# DigitalOutputs.net
KiCad netlist of a schematic drawn in Altium Designer
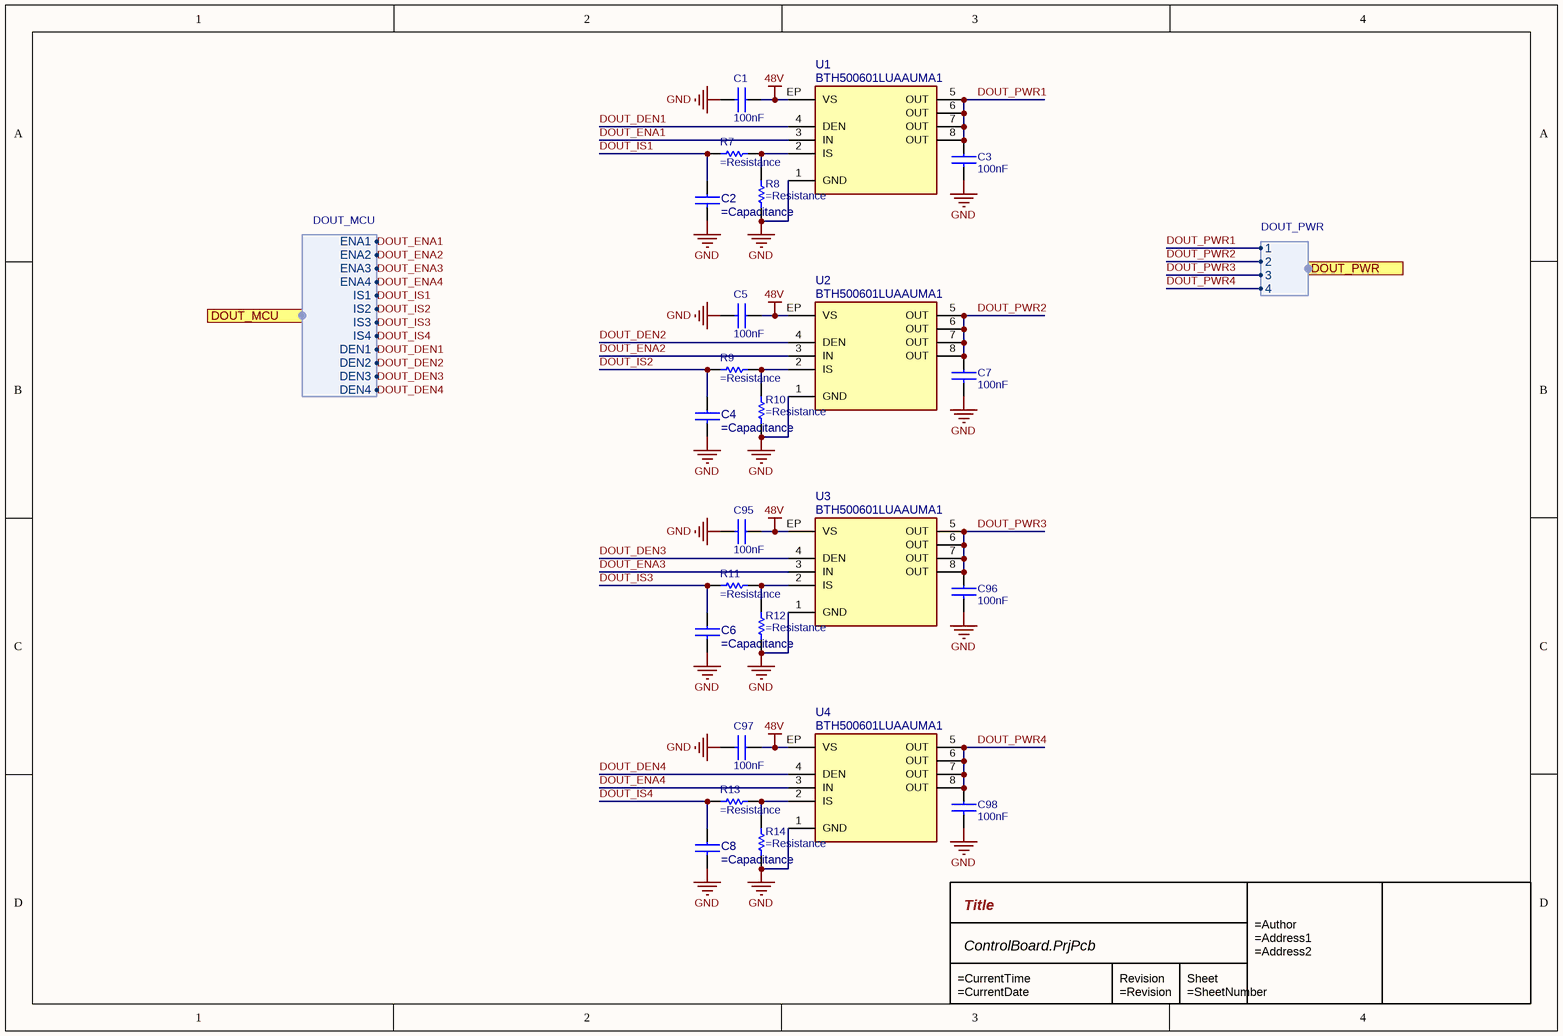
[diagram p0: DigitalOutputs.SchDoc]

(export (version "E")
  (design (tool "Eeschema 10.0.6"))
  (components
    (comp (ref "C1")
      (value "100nF")
      (footprint "C0603")
      (description "CAP CER 0.1UF 100V X7R 0603")
      (fields
        (field (name "MANUFACTURER") "Yageo")
        (field (name "MANUFACTURER PART NUMBER") "CC0603KRX7R0BB104")
      )
      (libsource (lib "Capacitors") (part "CAP0603-0.1uF-100V"))
    )
    (comp (ref "C2")
      (value "~")
      (footprint "C0402")
      (description "CAP CER 0.1UF 50V X7R 0402")
      (fields
        (field (name "MANUFACTURER") "Walsin Technologies")
        (field (name "MANUFACTURER PART NUMBER") "0402B104K500CT")
      )
      (libsource (lib "HerosLib") (part "CAP0402-0.1uF-50V"))
    )
    (comp (ref "C3")
      (value "100nF")
      (footprint "C0603")
      (description "CAP CER 0.1UF 100V X7R 0603")
      (fields
        (field (name "MANUFACTURER") "Yageo")
        (field (name "MANUFACTURER PART NUMBER") "CC0603KRX7R0BB104")
      )
      (libsource (lib "Capacitors") (part "CAP0603-0.1uF-100V"))
    )
    (comp (ref "C4")
      (value "~")
      (footprint "C0402")
      (description "CAP CER 0.1UF 50V X7R 0402")
      (fields
        (field (name "MANUFACTURER") "Walsin Technologies")
        (field (name "MANUFACTURER PART NUMBER") "0402B104K500CT")
      )
      (libsource (lib "HerosLib") (part "CAP0402-0.1uF-50V"))
    )
    (comp (ref "C5")
      (value "100nF")
      (footprint "C0603")
      (description "CAP CER 0.1UF 100V X7R 0603")
      (fields
        (field (name "MANUFACTURER") "Yageo")
        (field (name "MANUFACTURER PART NUMBER") "CC0603KRX7R0BB104")
      )
      (libsource (lib "Capacitors") (part "CAP0603-0.1uF-100V"))
    )
    (comp (ref "C6")
      (value "~")
      (footprint "C0402")
      (description "CAP CER 0.1UF 50V X7R 0402")
      (fields
        (field (name "MANUFACTURER") "Walsin Technologies")
        (field (name "MANUFACTURER PART NUMBER") "0402B104K500CT")
      )
      (libsource (lib "HerosLib") (part "CAP0402-0.1uF-50V"))
    )
    (comp (ref "C7")
      (value "100nF")
      (footprint "C0603")
      (description "CAP CER 0.1UF 100V X7R 0603")
      (fields
        (field (name "MANUFACTURER") "Yageo")
        (field (name "MANUFACTURER PART NUMBER") "CC0603KRX7R0BB104")
      )
      (libsource (lib "Capacitors") (part "CAP0603-0.1uF-100V"))
    )
    (comp (ref "C8")
      (value "~")
      (footprint "C0402")
      (description "CAP CER 0.1UF 50V X7R 0402")
      (fields
        (field (name "MANUFACTURER") "Walsin Technologies")
        (field (name "MANUFACTURER PART NUMBER") "0402B104K500CT")
      )
      (libsource (lib "HerosLib") (part "CAP0402-0.1uF-50V"))
    )
    (comp (ref "C95")
      (value "100nF")
      (footprint "C0603")
      (description "CAP CER 0.1UF 100V X7R 0603")
      (fields
        (field (name "MANUFACTURER") "Yageo")
        (field (name "MANUFACTURER PART NUMBER") "CC0603KRX7R0BB104")
      )
      (libsource (lib "Capacitors") (part "CAP0603-0.1uF-100V"))
    )
    (comp (ref "C96")
      (value "100nF")
      (footprint "C0603")
      (description "CAP CER 0.1UF 100V X7R 0603")
      (fields
        (field (name "MANUFACTURER") "Yageo")
        (field (name "MANUFACTURER PART NUMBER") "CC0603KRX7R0BB104")
      )
      (libsource (lib "Capacitors") (part "CAP0603-0.1uF-100V"))
    )
    (comp (ref "C97")
      (value "100nF")
      (footprint "C0603")
      (description "CAP CER 0.1UF 100V X7R 0603")
      (fields
        (field (name "MANUFACTURER") "Yageo")
        (field (name "MANUFACTURER PART NUMBER") "CC0603KRX7R0BB104")
      )
      (libsource (lib "Capacitors") (part "CAP0603-0.1uF-100V"))
    )
    (comp (ref "C98")
      (value "100nF")
      (footprint "C0603")
      (description "CAP CER 0.1UF 100V X7R 0603")
      (fields
        (field (name "MANUFACTURER") "Yageo")
        (field (name "MANUFACTURER PART NUMBER") "CC0603KRX7R0BB104")
      )
      (libsource (lib "Capacitors") (part "CAP0603-0.1uF-100V"))
    )
    (comp (ref "R7")
      (value "~")
      (footprint "R0402")
      (description "Res Thick Film 0402 1K Ohm 1% 0.063W(1/16W) ±50ppm/C Pad SMD Automotive T/R")
      (fields
        (field (name "MANUFACTURER") "Vishay")
        (field (name "MANUFACTURER PART NUMBER") "CRCW04021K00FHEDP")
      )
      (libsource (lib "Resistors") (part "RES0402-1k-1%"))
    )
    (comp (ref "R8")
      (value "~")
      (footprint "R0402")
      (description "Res Thick Film 0402 2K Ohm 1% 1/16W 100ppm/C Molded SMD SMD Paper T/R")
      (fields
        (field (name "MANUFACTURER") "Vishay")
        (field (name "MANUFACTURER PART NUMBER") "CRCW04022K00FKEE")
      )
      (libsource (lib "Resistors") (part "RES0402-2k-1%"))
    )
    (comp (ref "R9")
      (value "~")
      (footprint "R0402")
      (description "Res Thick Film 0402 1K Ohm 1% 0.063W(1/16W) ±50ppm/C Pad SMD Automotive T/R")
      (fields
        (field (name "MANUFACTURER") "Vishay")
        (field (name "MANUFACTURER PART NUMBER") "CRCW04021K00FHEDP")
      )
      (libsource (lib "Resistors") (part "RES0402-1k-1%"))
    )
    (comp (ref "R10")
      (value "~")
      (footprint "R0402")
      (description "Res Thick Film 0402 2K Ohm 1% 1/16W 100ppm/C Molded SMD SMD Paper T/R")
      (fields
        (field (name "MANUFACTURER") "Vishay")
        (field (name "MANUFACTURER PART NUMBER") "CRCW04022K00FKEE")
      )
      (libsource (lib "Resistors") (part "RES0402-2k-1%"))
    )
    (comp (ref "R11")
      (value "~")
      (footprint "R0402")
      (description "Res Thick Film 0402 1K Ohm 1% 0.063W(1/16W) ±50ppm/C Pad SMD Automotive T/R")
      (fields
        (field (name "MANUFACTURER") "Vishay")
        (field (name "MANUFACTURER PART NUMBER") "CRCW04021K00FHEDP")
      )
      (libsource (lib "Resistors") (part "RES0402-1k-1%"))
    )
    (comp (ref "R12")
      (value "~")
      (footprint "R0402")
      (description "Res Thick Film 0402 2K Ohm 1% 1/16W 100ppm/C Molded SMD SMD Paper T/R")
      (fields
        (field (name "MANUFACTURER") "Vishay")
        (field (name "MANUFACTURER PART NUMBER") "CRCW04022K00FKEE")
      )
      (libsource (lib "Resistors") (part "RES0402-2k-1%"))
    )
    (comp (ref "R13")
      (value "~")
      (footprint "R0402")
      (description "Res Thick Film 0402 1K Ohm 1% 0.063W(1/16W) ±50ppm/C Pad SMD Automotive T/R")
      (fields
        (field (name "MANUFACTURER") "Vishay")
        (field (name "MANUFACTURER PART NUMBER") "CRCW04021K00FHEDP")
      )
      (libsource (lib "Resistors") (part "RES0402-1k-1%"))
    )
    (comp (ref "R14")
      (value "~")
      (footprint "R0402")
      (description "Res Thick Film 0402 2K Ohm 1% 1/16W 100ppm/C Molded SMD SMD Paper T/R")
      (fields
        (field (name "MANUFACTURER") "Vishay")
        (field (name "MANUFACTURER PART NUMBER") "CRCW04022K00FKEE")
      )
      (libsource (lib "Resistors") (part "RES0402-2k-1%"))
    )
    (comp (ref "U1")
      (value "BTH500601LUAAUMA1")
      (footprint "PG-HSOF-8-1")
      (description "Power Load Sw, High Side, 150DEGC, HSOF8;")
      (fields (field (name "MANUFACTURER") "Infineon"))
      (libsource (lib "HerosLib") (part "BTH50060-1LUA"))
    )
    (comp (ref "U2")
      (value "BTH500601LUAAUMA1")
      (footprint "PG-HSOF-8-1")
      (description "Power Load Sw, High Side, 150DEGC, HSOF8;")
      (fields (field (name "MANUFACTURER") "Infineon"))
      (libsource (lib "HerosLib") (part "BTH50060-1LUA"))
    )
    (comp (ref "U3")
      (value "BTH500601LUAAUMA1")
      (footprint "PG-HSOF-8-1")
      (description "Power Load Sw, High Side, 150DEGC, HSOF8;")
      (fields (field (name "MANUFACTURER") "Infineon"))
      (libsource (lib "HerosLib") (part "BTH50060-1LUA"))
    )
    (comp (ref "U4")
      (value "BTH500601LUAAUMA1")
      (footprint "PG-HSOF-8-1")
      (description "Power Load Sw, High Side, 150DEGC, HSOF8;")
      (fields (field (name "MANUFACTURER") "Infineon"))
      (libsource (lib "HerosLib") (part "BTH50060-1LUA"))
    )
  )
  (nets
    (net (code "3") (name "/DOUT_DEN1") (class "Default")
      (node (ref "U1") (pin "4") (pinfunction "DEN_4") (pintype "passive"))
    )
    (net (code "4") (name "/DOUT_DEN2") (class "Default")
      (node (ref "U2") (pin "4") (pinfunction "DEN_4") (pintype "passive"))
    )
    (net (code "5") (name "/DOUT_DEN3") (class "Default")
      (node (ref "U3") (pin "4") (pinfunction "DEN_4") (pintype "passive"))
    )
    (net (code "6") (name "/DOUT_DEN4") (class "Default")
      (node (ref "U4") (pin "4") (pinfunction "DEN_4") (pintype "passive"))
    )
    (net (code "7") (name "/DOUT_ENA1") (class "Default")
      (node (ref "U1") (pin "3") (pinfunction "IN_3") (pintype "passive"))
    )
    (net (code "8") (name "/DOUT_ENA2") (class "Default")
      (node (ref "U2") (pin "3") (pinfunction "IN_3") (pintype "passive"))
    )
    (net (code "9") (name "/DOUT_ENA3") (class "Default")
      (node (ref "U3") (pin "3") (pinfunction "IN_3") (pintype "passive"))
    )
    (net (code "10") (name "/DOUT_ENA4") (class "Default")
      (node (ref "U4") (pin "3") (pinfunction "IN_3") (pintype "passive"))
    )
    (net (code "11") (name "/DOUT_IS1") (class "Default")
      (node (ref "C2") (pin "1") (pinfunction "1_1") (pintype "passive"))
      (node (ref "R7") (pin "1") (pinfunction "1_1") (pintype "passive"))
    )
    (net (code "12") (name "/DOUT_IS2") (class "Default")
      (node (ref "C4") (pin "1") (pinfunction "1_1") (pintype "passive"))
      (node (ref "R9") (pin "1") (pinfunction "1_1") (pintype "passive"))
    )
    (net (code "13") (name "/DOUT_IS3") (class "Default")
      (node (ref "C6") (pin "1") (pinfunction "1_1") (pintype "passive"))
      (node (ref "R11") (pin "1") (pinfunction "1_1") (pintype "passive"))
    )
    (net (code "14") (name "/DOUT_IS4") (class "Default")
      (node (ref "C8") (pin "1") (pinfunction "1_1") (pintype "passive"))
      (node (ref "R13") (pin "1") (pinfunction "1_1") (pintype "passive"))
    )
    (net (code "15") (name "/DOUT_PWR1") (class "Default")
      (node (ref "C3") (pin "1") (pinfunction "1_1") (pintype "passive"))
      (node (ref "U1") (pin "5") (pinfunction "OUT_5") (pintype "passive"))
      (node (ref "U1") (pin "6") (pinfunction "OUT_6") (pintype "passive"))
      (node (ref "U1") (pin "7") (pinfunction "OUT_7") (pintype "passive"))
      (node (ref "U1") (pin "8") (pinfunction "OUT_8") (pintype "passive"))
    )
    (net (code "16") (name "/DOUT_PWR2") (class "Default")
      (node (ref "C7") (pin "1") (pinfunction "1_1") (pintype "passive"))
      (node (ref "U2") (pin "5") (pinfunction "OUT_5") (pintype "passive"))
      (node (ref "U2") (pin "6") (pinfunction "OUT_6") (pintype "passive"))
      (node (ref "U2") (pin "7") (pinfunction "OUT_7") (pintype "passive"))
      (node (ref "U2") (pin "8") (pinfunction "OUT_8") (pintype "passive"))
    )
    (net (code "17") (name "/DOUT_PWR3") (class "Default")
      (node (ref "C96") (pin "1") (pinfunction "1_1") (pintype "passive"))
      (node (ref "U3") (pin "5") (pinfunction "OUT_5") (pintype "passive"))
      (node (ref "U3") (pin "6") (pinfunction "OUT_6") (pintype "passive"))
      (node (ref "U3") (pin "7") (pinfunction "OUT_7") (pintype "passive"))
      (node (ref "U3") (pin "8") (pinfunction "OUT_8") (pintype "passive"))
    )
    (net (code "18") (name "/DOUT_PWR4") (class "Default")
      (node (ref "C98") (pin "1") (pinfunction "1_1") (pintype "passive"))
      (node (ref "U4") (pin "5") (pinfunction "OUT_5") (pintype "passive"))
      (node (ref "U4") (pin "6") (pinfunction "OUT_6") (pintype "passive"))
      (node (ref "U4") (pin "7") (pinfunction "OUT_7") (pintype "passive"))
      (node (ref "U4") (pin "8") (pinfunction "OUT_8") (pintype "passive"))
    )
    (net (code "21") (name "48V") (class "Default")
      (node (ref "C1") (pin "1") (pinfunction "1_1") (pintype "passive"))
      (node (ref "C5") (pin "1") (pinfunction "1_1") (pintype "passive"))
      (node (ref "C95") (pin "1") (pinfunction "1_1") (pintype "passive"))
      (node (ref "C97") (pin "1") (pinfunction "1_1") (pintype "passive"))
      (node (ref "U1") (pin "EP") (pinfunction "VS_EP") (pintype "passive"))
      (node (ref "U2") (pin "EP") (pinfunction "VS_EP") (pintype "passive"))
      (node (ref "U3") (pin "EP") (pinfunction "VS_EP") (pintype "passive"))
      (node (ref "U4") (pin "EP") (pinfunction "VS_EP") (pintype "passive"))
    )
    (net (code "22") (name "GND") (class "Default")
      (node (ref "C1") (pin "2") (pinfunction "2_2") (pintype "passive"))
      (node (ref "C2") (pin "2") (pinfunction "2_2") (pintype "passive"))
      (node (ref "C3") (pin "2") (pinfunction "2_2") (pintype "passive"))
      (node (ref "C4") (pin "2") (pinfunction "2_2") (pintype "passive"))
      (node (ref "C5") (pin "2") (pinfunction "2_2") (pintype "passive"))
      (node (ref "C6") (pin "2") (pinfunction "2_2") (pintype "passive"))
      (node (ref "C7") (pin "2") (pinfunction "2_2") (pintype "passive"))
      (node (ref "C8") (pin "2") (pinfunction "2_2") (pintype "passive"))
      (node (ref "C95") (pin "2") (pinfunction "2_2") (pintype "passive"))
      (node (ref "C96") (pin "2") (pinfunction "2_2") (pintype "passive"))
      (node (ref "C97") (pin "2") (pinfunction "2_2") (pintype "passive"))
      (node (ref "C98") (pin "2") (pinfunction "2_2") (pintype "passive"))
      (node (ref "R10") (pin "1") (pinfunction "1_1") (pintype "passive"))
      (node (ref "R12") (pin "1") (pinfunction "1_1") (pintype "passive"))
      (node (ref "R14") (pin "1") (pinfunction "1_1") (pintype "passive"))
      (node (ref "R8") (pin "1") (pinfunction "1_1") (pintype "passive"))
      (node (ref "U1") (pin "1") (pinfunction "GND_1") (pintype "passive"))
      (node (ref "U2") (pin "1") (pinfunction "GND_1") (pintype "passive"))
      (node (ref "U3") (pin "1") (pinfunction "GND_1") (pintype "passive"))
      (node (ref "U4") (pin "1") (pinfunction "GND_1") (pintype "passive"))
    )
    (net (code "23") (name "Net-(U1-IS)") (class "Default")
      (node (ref "R7") (pin "2") (pinfunction "2_2") (pintype "passive"))
      (node (ref "R8") (pin "2") (pinfunction "2_2") (pintype "passive"))
      (node (ref "U1") (pin "2") (pinfunction "IS_2") (pintype "passive"))
    )
    (net (code "24") (name "Net-(U2-IS)") (class "Default")
      (node (ref "R10") (pin "2") (pinfunction "2_2") (pintype "passive"))
      (node (ref "R9") (pin "2") (pinfunction "2_2") (pintype "passive"))
      (node (ref "U2") (pin "2") (pinfunction "IS_2") (pintype "passive"))
    )
    (net (code "25") (name "Net-(U3-IS)") (class "Default")
      (node (ref "R11") (pin "2") (pinfunction "2_2") (pintype "passive"))
      (node (ref "R12") (pin "2") (pinfunction "2_2") (pintype "passive"))
      (node (ref "U3") (pin "2") (pinfunction "IS_2") (pintype "passive"))
    )
    (net (code "26") (name "Net-(U4-IS)") (class "Default")
      (node (ref "R13") (pin "2") (pinfunction "2_2") (pintype "passive"))
      (node (ref "R14") (pin "2") (pinfunction "2_2") (pintype "passive"))
      (node (ref "U4") (pin "2") (pinfunction "IS_2") (pintype "passive"))
    )
  )
)
